# mq3Circuit.net
KiCad netlist of a schematic drawn in EAGLE
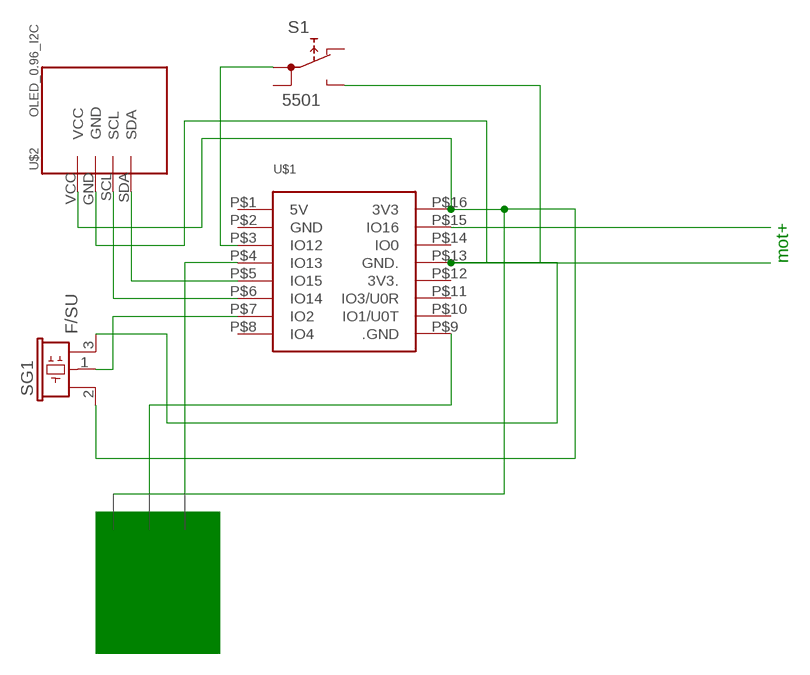
[diagram p0: schematic, sheet 1]

(export (version "E")
  (design (tool "Eeschema 10.0.6"))
  (components
    (comp (ref "S1")
      (value "5501")
      (footprint "eagle-import:5501")
      (libsource (lib "eagle-import") (part "55?01"))
    )
    (comp (ref "SG1")
      (value "F/SU")
      (footprint "eagle-import:F_SU")
      (libsource (lib "eagle-import") (part "F/SU"))
    )
    (comp (ref "U$1")
      (value "ESP32-CAM")
      (footprint "eagle-import:ESP32-CAM")
      (fields (field (name "MF") "AI-Thinker"))
      (libsource (lib "eagle-import") (part "ESP32-CAM"))
    )
    (comp (ref "U$2")
      (value "OLED_0.96_I2C")
      (footprint "eagle-import:OLED_0.96_I2C")
      (libsource (lib "eagle-import") (part "OLED_0.96_I2C"))
    )
  )
  (nets
    (net (code "1") (name "Net-(U$1-3V3)") (class "Default")
      (node (ref "SG1") (pin "2") (pinfunction "2_2") (pintype "passive"))
      (node (ref "U$1") (pin "P$16") (pinfunction "3V3_P$16") (pintype "bidirectional"))
      (node (ref "U$2") (pin "VCC") (pinfunction "VCC_VCC") (pintype "bidirectional"))
    )
    (net (code "2") (name "Net-(U$1-GND.)") (class "Default")
      (node (ref "S1") (pin "NO") (pinfunction "NO_NO") (pintype "passive"))
      (node (ref "SG1") (pin "3") (pinfunction "3_3") (pintype "passive"))
      (node (ref "U$1") (pin "P$13") (pinfunction "GND._P$13") (pintype "bidirectional"))
      (node (ref "U$2") (pin "GND") (pinfunction "GND_GND") (pintype "bidirectional"))
    )
    (net (code "3") (name "Net-(U$1-IO2)") (class "Default")
      (node (ref "SG1") (pin "1") (pinfunction "1_1") (pintype "passive"))
      (node (ref "U$1") (pin "P$7") (pinfunction "IO2_P$7") (pintype "bidirectional"))
    )
    (net (code "4") (name "Net-(U$1-IO12)") (class "Default")
      (node (ref "S1") (pin "1A") (pinfunction "1A_1A") (pintype "passive"))
      (node (ref "U$1") (pin "P$3") (pinfunction "IO12_P$3") (pintype "bidirectional"))
    )
    (net (code "5") (name "Net-(U$1-IO14)") (class "Default")
      (node (ref "U$1") (pin "P$6") (pinfunction "IO14_P$6") (pintype "bidirectional"))
      (node (ref "U$2") (pin "SCL") (pinfunction "SCL_SCL") (pintype "bidirectional"))
    )
    (net (code "6") (name "Net-(U$1-IO15)") (class "Default")
      (node (ref "U$1") (pin "P$5") (pinfunction "IO15_P$5") (pintype "bidirectional"))
      (node (ref "U$2") (pin "SDA") (pinfunction "SDA_SDA") (pintype "bidirectional"))
    )
    (net (code "7") (name "unconnected-(S1-Pad1B)") (class "Default")
      (node (ref "S1") (pin "1B") (pinfunction "1B_1B") (pintype "passive"))
    )
    (net (code "8") (name "unconnected-(S1-PadNC)") (class "Default")
      (node (ref "S1") (pin "NC") (pinfunction "NC_NC") (pintype "passive"))
    )
    (net (code "9") (name "unconnected-(U$1-.GND-PadP$9)") (class "Default")
      (node (ref "U$1") (pin "P$9") (pinfunction ".GND_P$9") (pintype "bidirectional"))
    )
    (net (code "10") (name "unconnected-(U$1-3V3.-PadP$12)") (class "Default")
      (node (ref "U$1") (pin "P$12") (pinfunction "3V3._P$12") (pintype "bidirectional"))
    )
    (net (code "11") (name "unconnected-(U$1-5V-PadP$1)") (class "Default")
      (node (ref "U$1") (pin "P$1") (pinfunction "5V_P$1") (pintype "bidirectional"))
    )
    (net (code "12") (name "unconnected-(U$1-GND-PadP$2)") (class "Default")
      (node (ref "U$1") (pin "P$2") (pinfunction "GND_P$2") (pintype "bidirectional"))
    )
    (net (code "13") (name "unconnected-(U$1-IO0-PadP$14)") (class "Default")
      (node (ref "U$1") (pin "P$14") (pinfunction "IO0_P$14") (pintype "bidirectional"))
    )
    (net (code "14") (name "unconnected-(U$1-IO1{slash}U0T-PadP$10)") (class "Default")
      (node (ref "U$1") (pin "P$10") (pinfunction "IO1/U0T_P$10") (pintype "bidirectional"))
    )
    (net (code "15") (name "unconnected-(U$1-IO3{slash}U0R-PadP$11)") (class "Default")
      (node (ref "U$1") (pin "P$11") (pinfunction "IO3/U0R_P$11") (pintype "bidirectional"))
    )
    (net (code "16") (name "unconnected-(U$1-IO4-PadP$8)") (class "Default")
      (node (ref "U$1") (pin "P$8") (pinfunction "IO4_P$8") (pintype "bidirectional"))
    )
    (net (code "17") (name "unconnected-(U$1-IO13-PadP$4)") (class "Default")
      (node (ref "U$1") (pin "P$4") (pinfunction "IO13_P$4") (pintype "bidirectional"))
    )
    (net (code "18") (name "unconnected-(U$1-IO16-PadP$15)") (class "Default")
      (node (ref "U$1") (pin "P$15") (pinfunction "IO16_P$15") (pintype "bidirectional"))
    )
  )
)
